# DETECT05.net
KiCad netlist of a schematic drawn in EAGLE
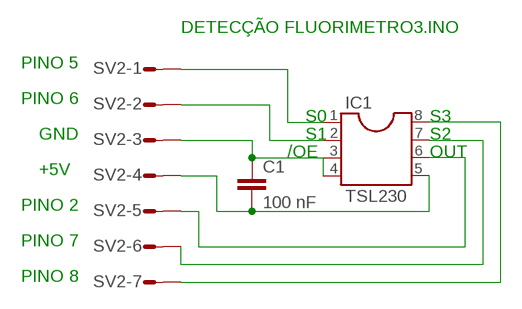
[diagram p0: schematic, sheet 1]

(export (version "E")
  (design (tool "Eeschema 10.0.6"))
  (components
    (comp (ref "C1")
      (value "100 nF")
      (footprint "eagle-import:C050-030X075")
      (libsource (lib "eagle-import") (part "C-EU050-030X075"))
    )
    (comp (ref "IC1")
      (value "TSL230")
      (footprint "eagle-import:DIL08")
      (libsource (lib "eagle-import") (part "DIL8"))
    )
    (comp (ref "SV2")
      (value "L07P")
      (footprint "eagle-import:L07P")
      (libsource (lib "eagle-import") (part "L07P"))
    )
  )
  (nets
    (net (code "1") (name "Net-(SV2A-S)") (class "Default")
      (node (ref "IC1") (pin "1") (pinfunction "1_1") (pintype "passive"))
      (node (ref "SV2") (pin "1") (pinfunction "S_1") (pintype "passive"))
    )
    (net (code "2") (name "Net-(SV2B-S)") (class "Default")
      (node (ref "IC1") (pin "2") (pinfunction "2_2") (pintype "passive"))
      (node (ref "SV2") (pin "2") (pinfunction "S_2") (pintype "passive"))
    )
    (net (code "3") (name "Net-(SV2C-S)") (class "Default")
      (node (ref "C1") (pin "1") (pinfunction "1_1") (pintype "passive"))
      (node (ref "IC1") (pin "3") (pinfunction "3_3") (pintype "passive"))
      (node (ref "IC1") (pin "4") (pinfunction "4_4") (pintype "passive"))
      (node (ref "SV2") (pin "3") (pinfunction "S_3") (pintype "passive"))
    )
    (net (code "4") (name "Net-(SV2D-S)") (class "Default")
      (node (ref "C1") (pin "2") (pinfunction "2_2") (pintype "passive"))
      (node (ref "IC1") (pin "5") (pinfunction "5_5") (pintype "passive"))
      (node (ref "SV2") (pin "4") (pinfunction "S_4") (pintype "passive"))
    )
    (net (code "5") (name "Net-(SV2E-S)") (class "Default")
      (node (ref "IC1") (pin "6") (pinfunction "6_6") (pintype "passive"))
      (node (ref "SV2") (pin "5") (pinfunction "S_5") (pintype "passive"))
    )
    (net (code "6") (name "Net-(SV2F-S)") (class "Default")
      (node (ref "IC1") (pin "7") (pinfunction "7_7") (pintype "passive"))
      (node (ref "SV2") (pin "6") (pinfunction "S_6") (pintype "passive"))
    )
    (net (code "7") (name "Net-(SV2G-S)") (class "Default")
      (node (ref "IC1") (pin "8") (pinfunction "8_8") (pintype "passive"))
      (node (ref "SV2") (pin "7") (pinfunction "S_7") (pintype "passive"))
    )
  )
)
